# GD32F450_Main_Board_Camera__V1_0.net
KiCad netlist of a schematic drawn in Altium Designer
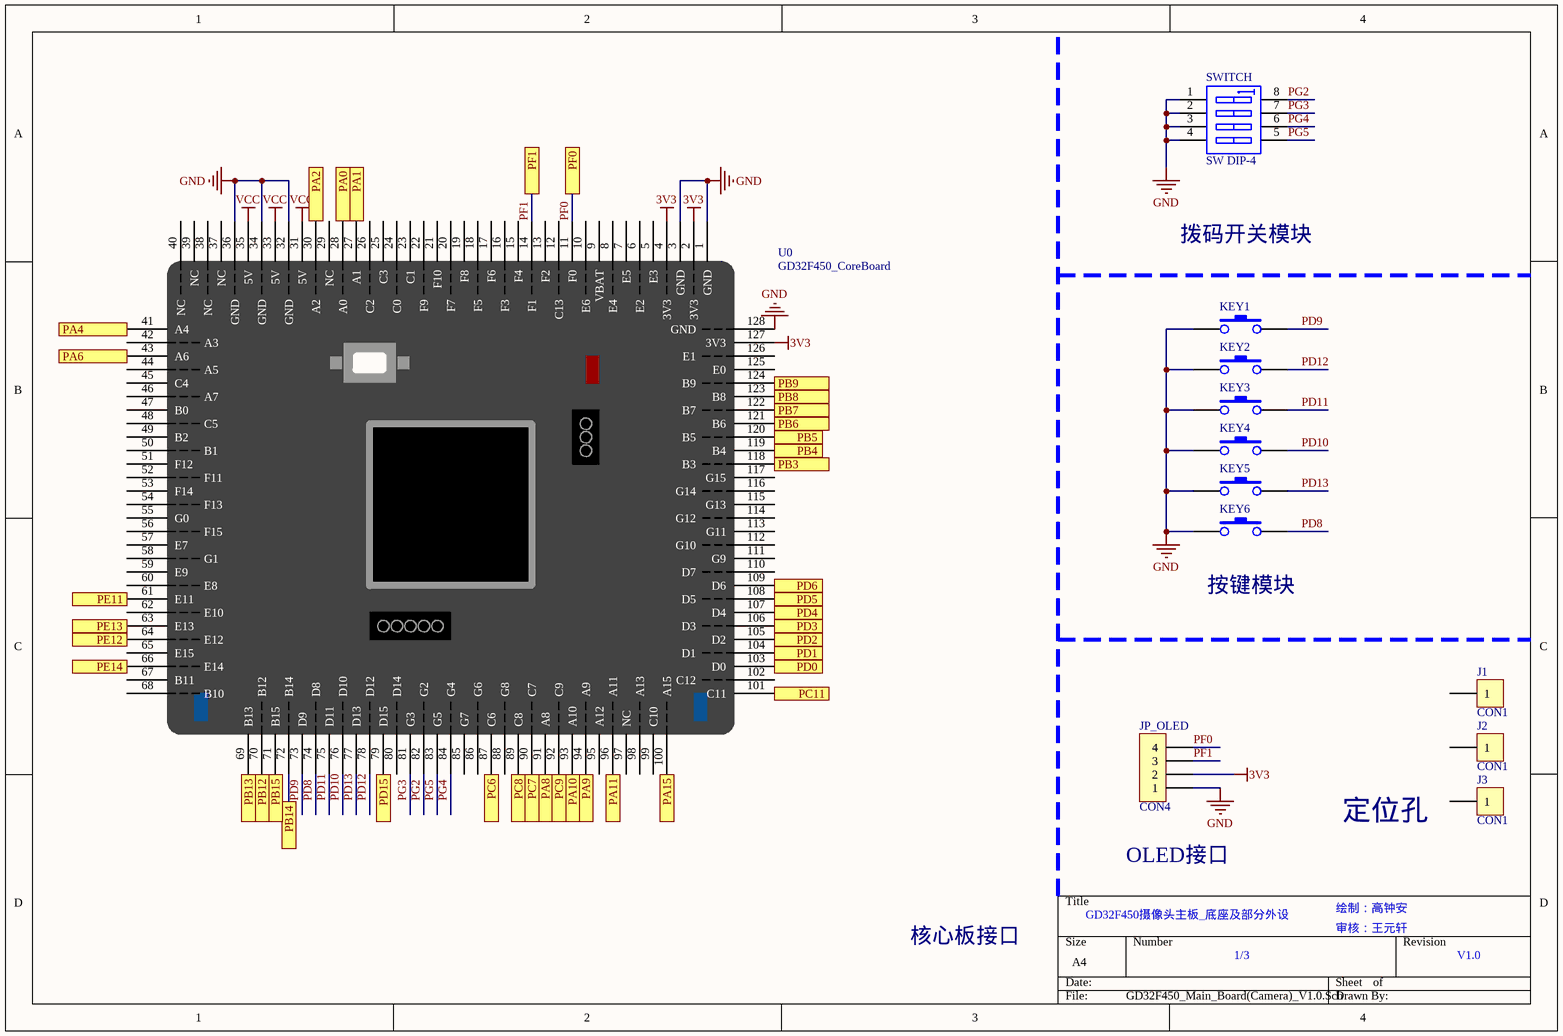
[diagram p0: GD32F450_Main_Board(Camera)_V1.0.SchDoc]

(export (version "E")
  (design (tool "Eeschema 10.0.6"))
  (components
    (comp (ref "J1")
      (value "CON1")
      (footprint "HOLE-3.5")
      (description "Connector")
      (libsource (lib "Protel99Lib_SCH") (part "CON1"))
    )
    (comp (ref "J2")
      (value "CON1")
      (footprint "HOLE-3.5")
      (description "Connector")
      (libsource (lib "Protel99Lib_SCH") (part "CON1"))
    )
    (comp (ref "J3")
      (value "CON1")
      (footprint "HOLE-3.5")
      (description "Connector")
      (libsource (lib "Protel99Lib_SCH") (part "CON1"))
    )
    (comp (ref "JP_OLED")
      (value "CON4")
      (footprint "OLED")
      (description "Connector")
      (libsource (lib "Protel99Lib_SCH") (part "CON4"))
    )
    (comp (ref "KEY1")
      (value "SW-PB")
      (footprint "KEY2-6X3")
      (libsource (lib "Protel99Lib_SCH") (part "SW-PB"))
    )
    (comp (ref "KEY2")
      (value "SW-PB")
      (footprint "KEY2-6X3")
      (libsource (lib "Protel99Lib_SCH") (part "SW-PB"))
    )
    (comp (ref "KEY3")
      (value "SW-PB")
      (footprint "KEY2-6X3")
      (libsource (lib "Protel99Lib_SCH") (part "SW-PB"))
    )
    (comp (ref "KEY4")
      (value "SW-PB")
      (footprint "KEY2-6X3")
      (libsource (lib "Protel99Lib_SCH") (part "SW-PB"))
    )
    (comp (ref "KEY5")
      (value "SW-PB")
      (footprint "KEY2-6X3")
      (libsource (lib "Protel99Lib_SCH") (part "SW-PB"))
    )
    (comp (ref "KEY6")
      (value "SW-PB")
      (footprint "KEY2-6X3")
      (libsource (lib "Protel99Lib_SCH") (part "SW-PB"))
    )
    (comp (ref "SWITCH")
      (value "SW DIP-4")
      (footprint "CSW DIP-4P")
      (description "DIP Switch")
      (libsource (lib "Protel99Lib_SCH") (part "SW DIP-4"))
    )
    (comp (ref "U0")
      (value "GD32F450_CoreBoard")
      (footprint "GD32F450_CoreBoard")
      (libsource (lib "GD32F450核心板整体封装") (part "GD32F450_CoreBoard"))
    )
  )
  (nets
    (net (code "1") (name "/PA0") (class "Default")
      (node (ref "U0") (pin "28") (pinfunction "A0_28") (pintype "passive"))
    )
    (net (code "2") (name "/PA1") (class "Default")
      (node (ref "U0") (pin "27") (pinfunction "A1_27") (pintype "passive"))
    )
    (net (code "3") (name "/PA2") (class "Default")
      (node (ref "U0") (pin "30") (pinfunction "A2_30") (pintype "passive"))
    )
    (net (code "4") (name "/PA4") (class "Default")
      (node (ref "U0") (pin "41") (pinfunction "A4_41") (pintype "passive"))
    )
    (net (code "5") (name "/PA6") (class "Default")
      (node (ref "U0") (pin "43") (pinfunction "A6_43") (pintype "passive"))
    )
    (net (code "6") (name "/PA8") (class "Default")
      (node (ref "U0") (pin "91") (pinfunction "A8_91") (pintype "passive"))
    )
    (net (code "7") (name "/PA9") (class "Default")
      (node (ref "U0") (pin "94") (pinfunction "A9_94") (pintype "passive"))
    )
    (net (code "8") (name "/PA10") (class "Default")
      (node (ref "U0") (pin "93") (pinfunction "A10_93") (pintype "passive"))
    )
    (net (code "9") (name "/PA11") (class "Default")
      (node (ref "U0") (pin "96") (pinfunction "A11_96") (pintype "passive"))
    )
    (net (code "10") (name "/PA15") (class "Default")
      (node (ref "U0") (pin "100") (pinfunction "A15_100") (pintype "passive"))
    )
    (net (code "11") (name "/PB3") (class "Default")
      (node (ref "U0") (pin "118") (pinfunction "B3_118") (pintype "passive"))
    )
    (net (code "12") (name "/PB4") (class "Default")
      (node (ref "U0") (pin "119") (pinfunction "B4_119") (pintype "passive"))
    )
    (net (code "13") (name "/PB5") (class "Default")
      (node (ref "U0") (pin "120") (pinfunction "B5_120") (pintype "passive"))
    )
    (net (code "14") (name "/PB6") (class "Default")
      (node (ref "U0") (pin "121") (pinfunction "B6_121") (pintype "passive"))
    )
    (net (code "15") (name "/PB7") (class "Default")
      (node (ref "U0") (pin "122") (pinfunction "B7_122") (pintype "passive"))
    )
    (net (code "16") (name "/PB8") (class "Default")
      (node (ref "U0") (pin "123") (pinfunction "B8_123") (pintype "passive"))
    )
    (net (code "17") (name "/PB9") (class "Default")
      (node (ref "U0") (pin "124") (pinfunction "B9_124") (pintype "passive"))
    )
    (net (code "18") (name "/PB12") (class "Default")
      (node (ref "U0") (pin "70") (pinfunction "B12_70") (pintype "passive"))
    )
    (net (code "19") (name "/PB13") (class "Default")
      (node (ref "U0") (pin "69") (pinfunction "B13_69") (pintype "passive"))
    )
    (net (code "20") (name "/PB14") (class "Default")
      (node (ref "U0") (pin "72") (pinfunction "B14_72") (pintype "passive"))
    )
    (net (code "21") (name "/PB15") (class "Default")
      (node (ref "U0") (pin "71") (pinfunction "B15_71") (pintype "passive"))
    )
    (net (code "22") (name "/PC6") (class "Default")
      (node (ref "U0") (pin "87") (pinfunction "C6_87") (pintype "passive"))
    )
    (net (code "23") (name "/PC7") (class "Default")
      (node (ref "U0") (pin "90") (pinfunction "C7_90") (pintype "passive"))
    )
    (net (code "24") (name "/PC8") (class "Default")
      (node (ref "U0") (pin "89") (pinfunction "C8_89") (pintype "passive"))
    )
    (net (code "25") (name "/PC9") (class "Default")
      (node (ref "U0") (pin "92") (pinfunction "C9_92") (pintype "passive"))
    )
    (net (code "26") (name "/PC11") (class "Default")
      (node (ref "U0") (pin "101") (pinfunction "C11_101") (pintype "passive"))
    )
    (net (code "27") (name "/PD0") (class "Default")
      (node (ref "U0") (pin "103") (pinfunction "D0_103") (pintype "passive"))
    )
    (net (code "28") (name "/PD1") (class "Default")
      (node (ref "U0") (pin "104") (pinfunction "D1_104") (pintype "passive"))
    )
    (net (code "29") (name "/PD2") (class "Default")
      (node (ref "U0") (pin "105") (pinfunction "D2_105") (pintype "passive"))
    )
    (net (code "30") (name "/PD3") (class "Default")
      (node (ref "U0") (pin "106") (pinfunction "D3_106") (pintype "passive"))
    )
    (net (code "31") (name "/PD4") (class "Default")
      (node (ref "U0") (pin "107") (pinfunction "D4_107") (pintype "passive"))
    )
    (net (code "32") (name "/PD5") (class "Default")
      (node (ref "U0") (pin "108") (pinfunction "D5_108") (pintype "passive"))
    )
    (net (code "33") (name "/PD6") (class "Default")
      (node (ref "U0") (pin "109") (pinfunction "D6_109") (pintype "passive"))
    )
    (net (code "34") (name "/PD8") (class "Default")
      (node (ref "KEY6") (pin "2") (pinfunction "2_2") (pintype "passive"))
      (node (ref "U0") (pin "74") (pinfunction "D8_74") (pintype "passive"))
    )
    (net (code "35") (name "/PD9") (class "Default")
      (node (ref "KEY1") (pin "2") (pinfunction "2_2") (pintype "passive"))
      (node (ref "U0") (pin "73") (pinfunction "D9_73") (pintype "passive"))
    )
    (net (code "36") (name "/PD10") (class "Default")
      (node (ref "KEY4") (pin "2") (pinfunction "2_2") (pintype "passive"))
      (node (ref "U0") (pin "76") (pinfunction "D10_76") (pintype "passive"))
    )
    (net (code "37") (name "/PD11") (class "Default")
      (node (ref "KEY3") (pin "2") (pinfunction "2_2") (pintype "passive"))
      (node (ref "U0") (pin "75") (pinfunction "D11_75") (pintype "passive"))
    )
    (net (code "38") (name "/PD12") (class "Default")
      (node (ref "KEY2") (pin "2") (pinfunction "2_2") (pintype "passive"))
      (node (ref "U0") (pin "78") (pinfunction "D12_78") (pintype "passive"))
    )
    (net (code "39") (name "/PD13") (class "Default")
      (node (ref "KEY5") (pin "2") (pinfunction "2_2") (pintype "passive"))
      (node (ref "U0") (pin "77") (pinfunction "D13_77") (pintype "passive"))
    )
    (net (code "40") (name "/PD15") (class "Default")
      (node (ref "U0") (pin "79") (pinfunction "D15_79") (pintype "passive"))
    )
    (net (code "41") (name "/PE11") (class "Default")
      (node (ref "U0") (pin "61") (pinfunction "E11_61") (pintype "passive"))
    )
    (net (code "42") (name "/PE12") (class "Default")
      (node (ref "U0") (pin "64") (pinfunction "E12_64") (pintype "passive"))
    )
    (net (code "43") (name "/PE13") (class "Default")
      (node (ref "U0") (pin "63") (pinfunction "E13_63") (pintype "passive"))
    )
    (net (code "44") (name "/PE14") (class "Default")
      (node (ref "U0") (pin "66") (pinfunction "E14_66") (pintype "passive"))
    )
    (net (code "45") (name "/PF0") (class "Default")
      (node (ref "JP_OLED") (pin "4") (pinfunction "4_4") (pintype "passive"))
      (node (ref "U0") (pin "11") (pinfunction "F0_11") (pintype "passive"))
    )
    (net (code "46") (name "/PF1") (class "Default")
      (node (ref "JP_OLED") (pin "3") (pinfunction "3_3") (pintype "passive"))
      (node (ref "U0") (pin "14") (pinfunction "F1_14") (pintype "passive"))
    )
    (net (code "47") (name "/PG2") (class "Default")
      (node (ref "SWITCH") (pin "8") (pinfunction "B1_8") (pintype "passive"))
      (node (ref "U0") (pin "82") (pinfunction "G2_82") (pintype "passive"))
    )
    (net (code "48") (name "/PG3") (class "Default")
      (node (ref "SWITCH") (pin "7") (pinfunction "B2_7") (pintype "passive"))
      (node (ref "U0") (pin "81") (pinfunction "G3_81") (pintype "passive"))
    )
    (net (code "49") (name "/PG4") (class "Default")
      (node (ref "SWITCH") (pin "6") (pinfunction "B3_6") (pintype "passive"))
      (node (ref "U0") (pin "84") (pinfunction "G4_84") (pintype "passive"))
    )
    (net (code "50") (name "/PG5") (class "Default")
      (node (ref "SWITCH") (pin "5") (pinfunction "B4_5") (pintype "passive"))
      (node (ref "U0") (pin "83") (pinfunction "G5_83") (pintype "passive"))
    )
    (net (code "51") (name "3V3") (class "Default")
      (node (ref "JP_OLED") (pin "2") (pinfunction "2_2") (pintype "passive"))
      (node (ref "U0") (pin "127") (pinfunction "3V3_127") (pintype "passive"))
      (node (ref "U0") (pin "2") (pinfunction "3V3_2") (pintype "passive"))
      (node (ref "U0") (pin "4") (pinfunction "3V3_4") (pintype "passive"))
    )
    (net (code "52") (name "GND") (class "Default")
      (node (ref "JP_OLED") (pin "1") (pinfunction "1_1") (pintype "passive"))
      (node (ref "KEY1") (pin "1") (pinfunction "1_1") (pintype "passive"))
      (node (ref "KEY2") (pin "1") (pinfunction "1_1") (pintype "passive"))
      (node (ref "KEY3") (pin "1") (pinfunction "1_1") (pintype "passive"))
      (node (ref "KEY4") (pin "1") (pinfunction "1_1") (pintype "passive"))
      (node (ref "KEY5") (pin "1") (pinfunction "1_1") (pintype "passive"))
      (node (ref "KEY6") (pin "1") (pinfunction "1_1") (pintype "passive"))
      (node (ref "SWITCH") (pin "1") (pinfunction "A1_1") (pintype "passive"))
      (node (ref "SWITCH") (pin "2") (pinfunction "A2_2") (pintype "passive"))
      (node (ref "SWITCH") (pin "3") (pinfunction "A3_3") (pintype "passive"))
      (node (ref "SWITCH") (pin "4") (pinfunction "A4_4") (pintype "passive"))
      (node (ref "U0") (pin "1") (pinfunction "GND_1") (pintype "passive"))
      (node (ref "U0") (pin "128") (pinfunction "GND_128") (pintype "passive"))
      (node (ref "U0") (pin "3") (pinfunction "GND_3") (pintype "passive"))
      (node (ref "U0") (pin "32") (pinfunction "GND_32") (pintype "passive"))
      (node (ref "U0") (pin "34") (pinfunction "GND_34") (pintype "passive"))
      (node (ref "U0") (pin "36") (pinfunction "GND_36") (pintype "passive"))
    )
    (net (code "53") (name "VCC") (class "Default")
      (node (ref "U0") (pin "31") (pinfunction "5V_31") (pintype "passive"))
      (node (ref "U0") (pin "33") (pinfunction "5V_33") (pintype "passive"))
      (node (ref "U0") (pin "35") (pinfunction "5V_35") (pintype "passive"))
    )
    (net (code "54") (name "unconnected-(J1-Pad1)") (class "Default")
      (node (ref "J1") (pin "1") (pinfunction "1_1") (pintype "passive"))
    )
    (net (code "55") (name "unconnected-(J2-Pad1)") (class "Default")
      (node (ref "J2") (pin "1") (pinfunction "1_1") (pintype "passive"))
    )
    (net (code "56") (name "unconnected-(J3-Pad1)") (class "Default")
      (node (ref "J3") (pin "1") (pinfunction "1_1") (pintype "passive"))
    )
    (net (code "57") (name "unconnected-(U0-A3-Pad42)") (class "Default")
      (node (ref "U0") (pin "42") (pinfunction "A3_42") (pintype "passive"))
    )
    (net (code "58") (name "unconnected-(U0-A5-Pad44)") (class "Default")
      (node (ref "U0") (pin "44") (pinfunction "A5_44") (pintype "passive"))
    )
    (net (code "59") (name "unconnected-(U0-A7-Pad46)") (class "Default")
      (node (ref "U0") (pin "46") (pinfunction "A7_46") (pintype "passive"))
    )
    (net (code "60") (name "unconnected-(U0-A12-Pad95)") (class "Default")
      (node (ref "U0") (pin "95") (pinfunction "A12_95") (pintype "passive"))
    )
    (net (code "61") (name "unconnected-(U0-A13-Pad98)") (class "Default")
      (node (ref "U0") (pin "98") (pinfunction "A13_98") (pintype "passive"))
    )
    (net (code "62") (name "unconnected-(U0-B0-Pad47)") (class "Default")
      (node (ref "U0") (pin "47") (pinfunction "B0_47") (pintype "passive"))
    )
    (net (code "63") (name "unconnected-(U0-B1-Pad50)") (class "Default")
      (node (ref "U0") (pin "50") (pinfunction "B1_50") (pintype "passive"))
    )
    (net (code "64") (name "unconnected-(U0-B2-Pad49)") (class "Default")
      (node (ref "U0") (pin "49") (pinfunction "B2_49") (pintype "passive"))
    )
    (net (code "65") (name "unconnected-(U0-B10-Pad68)") (class "Default")
      (node (ref "U0") (pin "68") (pinfunction "B10_68") (pintype "passive"))
    )
    (net (code "66") (name "unconnected-(U0-B11-Pad67)") (class "Default")
      (node (ref "U0") (pin "67") (pinfunction "B11_67") (pintype "passive"))
    )
    (net (code "67") (name "unconnected-(U0-C0-Pad24)") (class "Default")
      (node (ref "U0") (pin "24") (pinfunction "C0_24") (pintype "passive"))
    )
    (net (code "68") (name "unconnected-(U0-C1-Pad23)") (class "Default")
      (node (ref "U0") (pin "23") (pinfunction "C1_23") (pintype "passive"))
    )
    (net (code "69") (name "unconnected-(U0-C2-Pad26)") (class "Default")
      (node (ref "U0") (pin "26") (pinfunction "C2_26") (pintype "passive"))
    )
    (net (code "70") (name "unconnected-(U0-C3-Pad25)") (class "Default")
      (node (ref "U0") (pin "25") (pinfunction "C3_25") (pintype "passive"))
    )
    (net (code "71") (name "unconnected-(U0-C4-Pad45)") (class "Default")
      (node (ref "U0") (pin "45") (pinfunction "C4_45") (pintype "passive"))
    )
    (net (code "72") (name "unconnected-(U0-C5-Pad48)") (class "Default")
      (node (ref "U0") (pin "48") (pinfunction "C5_48") (pintype "passive"))
    )
    (net (code "73") (name "unconnected-(U0-C10-Pad99)") (class "Default")
      (node (ref "U0") (pin "99") (pinfunction "C10_99") (pintype "passive"))
    )
    (net (code "74") (name "unconnected-(U0-C12-Pad102)") (class "Default")
      (node (ref "U0") (pin "102") (pinfunction "C12_102") (pintype "passive"))
    )
    (net (code "75") (name "unconnected-(U0-C13-Pad12)") (class "Default")
      (node (ref "U0") (pin "12") (pinfunction "C13_12") (pintype "passive"))
    )
    (net (code "76") (name "unconnected-(U0-D7-Pad110)") (class "Default")
      (node (ref "U0") (pin "110") (pinfunction "D7_110") (pintype "passive"))
    )
    (net (code "77") (name "unconnected-(U0-D14-Pad80)") (class "Default")
      (node (ref "U0") (pin "80") (pinfunction "D14_80") (pintype "passive"))
    )
    (net (code "78") (name "unconnected-(U0-E0-Pad125)") (class "Default")
      (node (ref "U0") (pin "125") (pinfunction "E0_125") (pintype "passive"))
    )
    (net (code "79") (name "unconnected-(U0-E1-Pad126)") (class "Default")
      (node (ref "U0") (pin "126") (pinfunction "E1_126") (pintype "passive"))
    )
    (net (code "80") (name "unconnected-(U0-E2-Pad6)") (class "Default")
      (node (ref "U0") (pin "6") (pinfunction "E2_6") (pintype "passive"))
    )
    (net (code "81") (name "unconnected-(U0-E3-Pad5)") (class "Default")
      (node (ref "U0") (pin "5") (pinfunction "E3_5") (pintype "passive"))
    )
    (net (code "82") (name "unconnected-(U0-E4-Pad8)") (class "Default")
      (node (ref "U0") (pin "8") (pinfunction "E4_8") (pintype "passive"))
    )
    (net (code "83") (name "unconnected-(U0-E5-Pad7)") (class "Default")
      (node (ref "U0") (pin "7") (pinfunction "E5_7") (pintype "passive"))
    )
    (net (code "84") (name "unconnected-(U0-E6-Pad10)") (class "Default")
      (node (ref "U0") (pin "10") (pinfunction "E6_10") (pintype "passive"))
    )
    (net (code "85") (name "unconnected-(U0-E7-Pad57)") (class "Default")
      (node (ref "U0") (pin "57") (pinfunction "E7_57") (pintype "passive"))
    )
    (net (code "86") (name "unconnected-(U0-E8-Pad60)") (class "Default")
      (node (ref "U0") (pin "60") (pinfunction "E8_60") (pintype "passive"))
    )
    (net (code "87") (name "unconnected-(U0-E9-Pad59)") (class "Default")
      (node (ref "U0") (pin "59") (pinfunction "E9_59") (pintype "passive"))
    )
    (net (code "88") (name "unconnected-(U0-E10-Pad62)") (class "Default")
      (node (ref "U0") (pin "62") (pinfunction "E10_62") (pintype "passive"))
    )
    (net (code "89") (name "unconnected-(U0-E15-Pad65)") (class "Default")
      (node (ref "U0") (pin "65") (pinfunction "E15_65") (pintype "passive"))
    )
    (net (code "90") (name "unconnected-(U0-F2-Pad13)") (class "Default")
      (node (ref "U0") (pin "13") (pinfunction "F2_13") (pintype "passive"))
    )
    (net (code "91") (name "unconnected-(U0-F3-Pad16)") (class "Default")
      (node (ref "U0") (pin "16") (pinfunction "F3_16") (pintype "passive"))
    )
    (net (code "92") (name "unconnected-(U0-F4-Pad15)") (class "Default")
      (node (ref "U0") (pin "15") (pinfunction "F4_15") (pintype "passive"))
    )
    (net (code "93") (name "unconnected-(U0-F5-Pad18)") (class "Default")
      (node (ref "U0") (pin "18") (pinfunction "F5_18") (pintype "passive"))
    )
    (net (code "94") (name "unconnected-(U0-F6-Pad17)") (class "Default")
      (node (ref "U0") (pin "17") (pinfunction "F6_17") (pintype "passive"))
    )
    (net (code "95") (name "unconnected-(U0-F7-Pad20)") (class "Default")
      (node (ref "U0") (pin "20") (pinfunction "F7_20") (pintype "passive"))
    )
    (net (code "96") (name "unconnected-(U0-F8-Pad19)") (class "Default")
      (node (ref "U0") (pin "19") (pinfunction "F8_19") (pintype "passive"))
    )
    (net (code "97") (name "unconnected-(U0-F9-Pad22)") (class "Default")
      (node (ref "U0") (pin "22") (pinfunction "F9_22") (pintype "passive"))
    )
    (net (code "98") (name "unconnected-(U0-F10-Pad21)") (class "Default")
      (node (ref "U0") (pin "21") (pinfunction "F10_21") (pintype "passive"))
    )
    (net (code "99") (name "unconnected-(U0-F11-Pad52)") (class "Default")
      (node (ref "U0") (pin "52") (pinfunction "F11_52") (pintype "passive"))
    )
    (net (code "100") (name "unconnected-(U0-F12-Pad51)") (class "Default")
      (node (ref "U0") (pin "51") (pinfunction "F12_51") (pintype "passive"))
    )
    (net (code "101") (name "unconnected-(U0-F13-Pad54)") (class "Default")
      (node (ref "U0") (pin "54") (pinfunction "F13_54") (pintype "passive"))
    )
    (net (code "102") (name "unconnected-(U0-F14-Pad53)") (class "Default")
      (node (ref "U0") (pin "53") (pinfunction "F14_53") (pintype "passive"))
    )
    (net (code "103") (name "unconnected-(U0-F15-Pad56)") (class "Default")
      (node (ref "U0") (pin "56") (pinfunction "F15_56") (pintype "passive"))
    )
    (net (code "104") (name "unconnected-(U0-G0-Pad55)") (class "Default")
      (node (ref "U0") (pin "55") (pinfunction "G0_55") (pintype "passive"))
    )
    (net (code "105") (name "unconnected-(U0-G1-Pad58)") (class "Default")
      (node (ref "U0") (pin "58") (pinfunction "G1_58") (pintype "passive"))
    )
    (net (code "106") (name "unconnected-(U0-G6-Pad86)") (class "Default")
      (node (ref "U0") (pin "86") (pinfunction "G6_86") (pintype "passive"))
    )
    (net (code "107") (name "unconnected-(U0-G7-Pad85)") (class "Default")
      (node (ref "U0") (pin "85") (pinfunction "G7_85") (pintype "passive"))
    )
    (net (code "108") (name "unconnected-(U0-G8-Pad88)") (class "Default")
      (node (ref "U0") (pin "88") (pinfunction "G8_88") (pintype "passive"))
    )
    (net (code "109") (name "unconnected-(U0-G9-Pad111)") (class "Default")
      (node (ref "U0") (pin "111") (pinfunction "G9_111") (pintype "passive"))
    )
    (net (code "110") (name "unconnected-(U0-G10-Pad112)") (class "Default")
      (node (ref "U0") (pin "112") (pinfunction "G10_112") (pintype "passive"))
    )
    (net (code "111") (name "unconnected-(U0-G11-Pad113)") (class "Default")
      (node (ref "U0") (pin "113") (pinfunction "G11_113") (pintype "passive"))
    )
    (net (code "112") (name "unconnected-(U0-G12-Pad114)") (class "Default")
      (node (ref "U0") (pin "114") (pinfunction "G12_114") (pintype "passive"))
    )
    (net (code "113") (name "unconnected-(U0-G13-Pad115)") (class "Default")
      (node (ref "U0") (pin "115") (pinfunction "G13_115") (pintype "passive"))
    )
    (net (code "114") (name "unconnected-(U0-G14-Pad116)") (class "Default")
      (node (ref "U0") (pin "116") (pinfunction "G14_116") (pintype "passive"))
    )
    (net (code "115") (name "unconnected-(U0-G15-Pad117)") (class "Default")
      (node (ref "U0") (pin "117") (pinfunction "G15_117") (pintype "passive"))
    )
    (net (code "116") (name "unconnected-(U0-NC-Pad29)") (class "Default")
      (node (ref "U0") (pin "29") (pinfunction "NC_29") (pintype "passive"))
    )
    (net (code "117") (name "unconnected-(U0-NC-Pad37)") (class "Default")
      (node (ref "U0") (pin "37") (pinfunction "NC_37") (pintype "passive"))
    )
    (net (code "118") (name "unconnected-(U0-NC-Pad38)") (class "Default")
      (node (ref "U0") (pin "38") (pinfunction "NC_38") (pintype "passive"))
    )
    (net (code "119") (name "unconnected-(U0-NC-Pad39)") (class "Default")
      (node (ref "U0") (pin "39") (pinfunction "NC_39") (pintype "passive"))
    )
    (net (code "120") (name "unconnected-(U0-NC-Pad40)") (class "Default")
      (node (ref "U0") (pin "40") (pinfunction "NC_40") (pintype "passive"))
    )
    (net (code "121") (name "unconnected-(U0-NC-Pad97)") (class "Default")
      (node (ref "U0") (pin "97") (pinfunction "NC_97") (pintype "passive"))
    )
    (net (code "122") (name "unconnected-(U0-VBAT-Pad9)") (class "Default")
      (node (ref "U0") (pin "9") (pinfunction "VBAT_9") (pintype "passive"))
    )
  )
)
